# programmer-E01.net
KiCad netlist of a schematic drawn in EAGLE
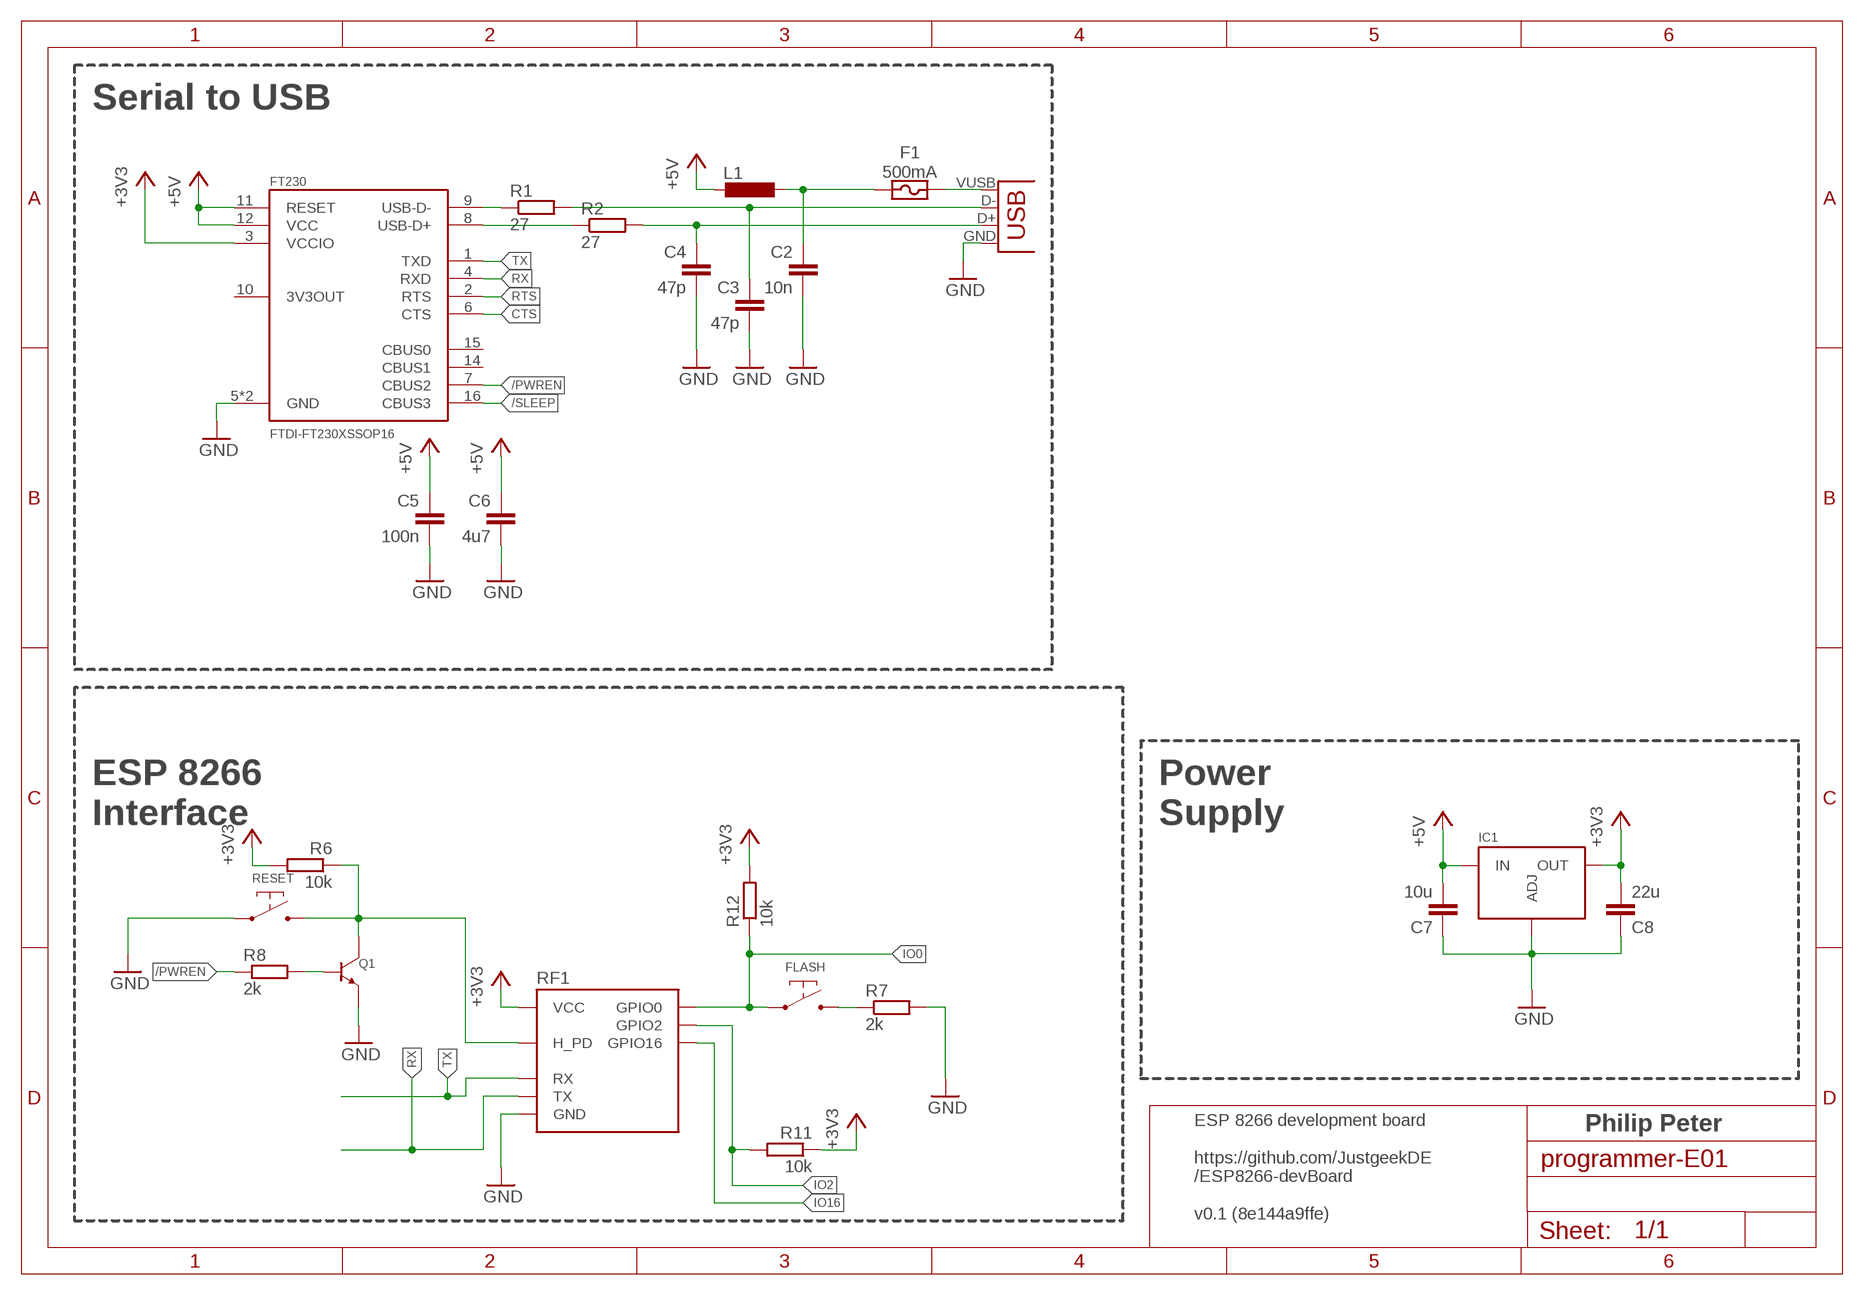
[diagram p0: schematic, sheet 1]

(export (version "E")
  (design (tool "Eeschema 10.0.6"))
  (components
    (comp (ref "C2")
      (value "10n")
      (footprint "eagle-import:C0805")
      (libsource (lib "eagle-import") (part "C-EUC0805"))
    )
    (comp (ref "C3")
      (value "47p")
      (footprint "eagle-import:C0805")
      (libsource (lib "eagle-import") (part "C-EUC0805"))
    )
    (comp (ref "C4")
      (value "47p")
      (footprint "eagle-import:C0805")
      (libsource (lib "eagle-import") (part "C-EUC0805"))
    )
    (comp (ref "C5")
      (value "100n")
      (footprint "eagle-import:C0805")
      (libsource (lib "eagle-import") (part "C-EUC0805"))
    )
    (comp (ref "C6")
      (value "4u7")
      (footprint "eagle-import:C0805")
      (libsource (lib "eagle-import") (part "C-EUC0805"))
    )
    (comp (ref "C7")
      (value "10u")
      (footprint "eagle-import:C0805")
      (libsource (lib "eagle-import") (part "C-EUC0805"))
    )
    (comp (ref "C8")
      (value "22u")
      (footprint "eagle-import:C0805")
      (libsource (lib "eagle-import") (part "C-EUC0805"))
    )
    (comp (ref "CON1")
      (value "USBMICRO-NO_CENTER-LONG_PADS")
      (footprint "eagle-import:USB-MICRO-SMD-NO_CENTER-LONG_PADS")
      (libsource (lib "eagle-import") (part "USBMICRO-NO_CENTER-LONG_PADS"))
    )
    (comp (ref "F1")
      (value "500mA")
      (footprint "eagle-import:SMD-FUSE-0805")
      (libsource (lib "eagle-import") (part "FUSE0805"))
    )
    (comp (ref "FLASH")
      (value "SWITCH-DEFAULT_OFF-2PIN")
      (footprint "eagle-import:SWITCH-GENERIC-2_PIN")
      (libsource (lib "eagle-import") (part "SWITCH-DEFAULT_OFF-2PIN"))
    )
    (comp (ref "FT230")
      (value "FTDI-FT230XSSOP16")
      (footprint "eagle-import:SSOP-16-FTDI")
      (libsource (lib "eagle-import") (part "FTDI-FT230XSSOP16"))
    )
    (comp (ref "IC1")
      (value "REGULATOR-LM317-SOT223")
      (footprint "eagle-import:SOT223")
      (libsource (lib "eagle-import") (part "REGULATOR-LM317-SOT223"))
    )
    (comp (ref "L1")
      (value "875-MI0805K601R-10")
      (footprint "eagle-import:R0805")
      (libsource (lib "eagle-import") (part "INDUCTOR0805"))
    )
    (comp (ref "Q1")
      (value "TRANSISTOR-NPN-GENERIC-SOT23-BEC")
      (footprint "eagle-import:SOT23")
      (libsource (lib "eagle-import") (part "TRANSISTOR-NPN-GENERIC-SOT23-BEC"))
    )
    (comp (ref "R1")
      (value "27")
      (footprint "eagle-import:R0805")
      (libsource (lib "eagle-import") (part "R-EU_R0805"))
    )
    (comp (ref "R2")
      (value "27")
      (footprint "eagle-import:R0805")
      (libsource (lib "eagle-import") (part "R-EU_R0805"))
    )
    (comp (ref "R6")
      (value "10k")
      (footprint "eagle-import:R0805")
      (libsource (lib "eagle-import") (part "R-EU_R0805"))
    )
    (comp (ref "R7")
      (value "2k")
      (footprint "eagle-import:R0805")
      (libsource (lib "eagle-import") (part "R-EU_R0805"))
    )
    (comp (ref "R8")
      (value "2k")
      (footprint "eagle-import:R0805")
      (libsource (lib "eagle-import") (part "R-EU_R0805"))
    )
    (comp (ref "R11")
      (value "10k")
      (footprint "eagle-import:R0805")
      (libsource (lib "eagle-import") (part "R-EU_R0805"))
    )
    (comp (ref "R12")
      (value "10k")
      (footprint "eagle-import:R0805")
      (libsource (lib "eagle-import") (part "R-EU_R0805"))
    )
    (comp (ref "RESET")
      (value "SWITCH-DEFAULT_OFF-2PIN")
      (footprint "eagle-import:SWITCH-GENERIC-2_PIN")
      (libsource (lib "eagle-import") (part "SWITCH-DEFAULT_OFF-2PIN"))
    )
    (comp (ref "RF1")
      (value "ESP2866-ESP-01THT")
      (footprint "eagle-import:ESP8266-ESP-01")
      (libsource (lib "eagle-import") (part "ESP2866-ESP-01THT"))
    )
  )
  (nets
    (net (code "1") (name "+3V3") (class "Default")
      (node (ref "C8") (pin "2") (pinfunction "2_2") (pintype "passive"))
      (node (ref "FT230") (pin "3") (pinfunction "VCCIO_3") (pintype "bidirectional"))
      (node (ref "IC1") (pin "2") (pinfunction "OUT_2") (pintype "bidirectional"))
      (node (ref "IC1") (pin "4") (pinfunction "OUT_4") (pintype "bidirectional"))
      (node (ref "R11") (pin "1") (pinfunction "1_1") (pintype "passive"))
      (node (ref "R12") (pin "2") (pinfunction "2_2") (pintype "passive"))
      (node (ref "R6") (pin "2") (pinfunction "2_2") (pintype "passive"))
      (node (ref "RF1") (pin "VCC") (pinfunction "VCC_VCC") (pintype "bidirectional"))
    )
    (net (code "2") (name "+5V") (class "Default")
      (node (ref "C5") (pin "1") (pinfunction "1_1") (pintype "passive"))
      (node (ref "C6") (pin "1") (pinfunction "1_1") (pintype "passive"))
      (node (ref "C7") (pin "2") (pinfunction "2_2") (pintype "passive"))
      (node (ref "FT230") (pin "11") (pinfunction "RESET_11") (pintype "bidirectional"))
      (node (ref "FT230") (pin "12") (pinfunction "VCC_12") (pintype "bidirectional"))
      (node (ref "IC1") (pin "3") (pinfunction "IN_3") (pintype "bidirectional"))
      (node (ref "L1") (pin "2") (pinfunction "2_2") (pintype "passive"))
    )
    (net (code "3") (name "CTS") (class "Default")
      (node (ref "FT230") (pin "6") (pinfunction "CTS_6") (pintype "bidirectional"))
    )
    (net (code "4") (name "GND") (class "Default")
      (node (ref "C2") (pin "2") (pinfunction "2_2") (pintype "passive"))
      (node (ref "C3") (pin "2") (pinfunction "2_2") (pintype "passive"))
      (node (ref "C4") (pin "2") (pinfunction "2_2") (pintype "passive"))
      (node (ref "C5") (pin "2") (pinfunction "2_2") (pintype "passive"))
      (node (ref "C6") (pin "2") (pinfunction "2_2") (pintype "passive"))
      (node (ref "C7") (pin "1") (pinfunction "1_1") (pintype "passive"))
      (node (ref "C8") (pin "1") (pinfunction "1_1") (pintype "passive"))
      (node (ref "CON1") (pin "GND") (pinfunction "GND_GND") (pintype "bidirectional"))
      (node (ref "FT230") (pin "13") (pinfunction "GND_13") (pintype "bidirectional"))
      (node (ref "FT230") (pin "5") (pinfunction "GND_5") (pintype "bidirectional"))
      (node (ref "IC1") (pin "1") (pinfunction "ADJ_1") (pintype "bidirectional"))
      (node (ref "Q1") (pin "P$2") (pinfunction "EMITTER_P$2") (pintype "bidirectional"))
      (node (ref "R7") (pin "2") (pinfunction "2_2") (pintype "passive"))
      (node (ref "RESET") (pin "P$1") (pinfunction "P$1_P$1") (pintype "bidirectional"))
      (node (ref "RF1") (pin "GND") (pinfunction "GND_GND") (pintype "bidirectional"))
    )
    (net (code "5") (name "IO0") (class "Default")
      (node (ref "FLASH") (pin "P$1") (pinfunction "P$1_P$1") (pintype "bidirectional"))
      (node (ref "R12") (pin "1") (pinfunction "1_1") (pintype "passive"))
      (node (ref "RF1") (pin "GPIO0") (pinfunction "GPIO0_GPIO0") (pintype "bidirectional"))
    )
    (net (code "6") (name "IO2") (class "Default")
      (node (ref "R11") (pin "2") (pinfunction "2_2") (pintype "passive"))
      (node (ref "RF1") (pin "GPIO2") (pinfunction "GPIO2_GPIO2") (pintype "bidirectional"))
    )
    (net (code "7") (name "IO16") (class "Default")
      (node (ref "RF1") (pin "GPIO16") (pinfunction "GPIO16_GPIO16") (pintype "bidirectional"))
    )
    (net (code "8") (name "Net-(C3-Pad1)") (class "Default")
      (node (ref "C3") (pin "1") (pinfunction "1_1") (pintype "passive"))
      (node (ref "CON1") (pin "D-") (pinfunction "D-_D-") (pintype "bidirectional"))
      (node (ref "R1") (pin "2") (pinfunction "2_2") (pintype "passive"))
    )
    (net (code "9") (name "Net-(C4-Pad1)") (class "Default")
      (node (ref "C4") (pin "1") (pinfunction "1_1") (pintype "passive"))
      (node (ref "CON1") (pin "D+") (pinfunction "D+_D+") (pintype "bidirectional"))
      (node (ref "R2") (pin "2") (pinfunction "2_2") (pintype "passive"))
    )
    (net (code "10") (name "Net-(CON1-VBUS)") (class "Default")
      (node (ref "CON1") (pin "VUSB") (pinfunction "VBUS_VUSB") (pintype "bidirectional"))
      (node (ref "F1") (pin "2") (pinfunction "P$2_2") (pintype "bidirectional"))
    )
    (net (code "11") (name "Net-(F1-P$1)") (class "Default")
      (node (ref "C2") (pin "1") (pinfunction "1_1") (pintype "passive"))
      (node (ref "F1") (pin "1") (pinfunction "P$1_1") (pintype "bidirectional"))
      (node (ref "L1") (pin "1") (pinfunction "1_1") (pintype "passive"))
    )
    (net (code "12") (name "Net-(FLASH-PadP$2)") (class "Default")
      (node (ref "FLASH") (pin "P$2") (pinfunction "P$2_P$2") (pintype "bidirectional"))
      (node (ref "R7") (pin "1") (pinfunction "1_1") (pintype "passive"))
    )
    (net (code "13") (name "Net-(FT230-USB-D+)") (class "Default")
      (node (ref "FT230") (pin "8") (pinfunction "USB-D+_8") (pintype "bidirectional"))
      (node (ref "R2") (pin "1") (pinfunction "1_1") (pintype "passive"))
    )
    (net (code "14") (name "Net-(FT230-USB-D-)") (class "Default")
      (node (ref "FT230") (pin "9") (pinfunction "USB-D-_9") (pintype "bidirectional"))
      (node (ref "R1") (pin "1") (pinfunction "1_1") (pintype "passive"))
    )
    (net (code "15") (name "Net-(Q1-BASE)") (class "Default")
      (node (ref "Q1") (pin "P$1") (pinfunction "BASE_P$1") (pintype "bidirectional"))
      (node (ref "R8") (pin "2") (pinfunction "2_2") (pintype "passive"))
    )
    (net (code "16") (name "Net-(Q1-COLLECTOR)") (class "Default")
      (node (ref "Q1") (pin "P$3") (pinfunction "COLLECTOR_P$3") (pintype "bidirectional"))
      (node (ref "R6") (pin "1") (pinfunction "1_1") (pintype "passive"))
      (node (ref "RESET") (pin "P$2") (pinfunction "P$2_P$2") (pintype "bidirectional"))
      (node (ref "RF1") (pin "H_PD") (pinfunction "H_PD_H_PD") (pintype "bidirectional"))
    )
    (net (code "17") (name "RTS") (class "Default")
      (node (ref "FT230") (pin "2") (pinfunction "RTS_2") (pintype "bidirectional"))
    )
    (net (code "18") (name "RX") (class "Default")
      (node (ref "FT230") (pin "4") (pinfunction "RXD_4") (pintype "bidirectional"))
      (node (ref "RF1") (pin "TX") (pinfunction "TX_TX") (pintype "bidirectional"))
    )
    (net (code "19") (name "TX") (class "Default")
      (node (ref "FT230") (pin "1") (pinfunction "TXD_1") (pintype "bidirectional"))
      (node (ref "RF1") (pin "RX") (pinfunction "RX_RX") (pintype "bidirectional"))
    )
    (net (code "20") (name "unconnected-(FT230-3V3OUT-Pad10)") (class "Default")
      (node (ref "FT230") (pin "10") (pinfunction "3V3OUT_10") (pintype "bidirectional"))
    )
    (net (code "21") (name "unconnected-(FT230-CBUS0-Pad15)") (class "Default")
      (node (ref "FT230") (pin "15") (pinfunction "CBUS0_15") (pintype "bidirectional"))
    )
    (net (code "22") (name "unconnected-(FT230-CBUS1-Pad14)") (class "Default")
      (node (ref "FT230") (pin "14") (pinfunction "CBUS1_14") (pintype "bidirectional"))
    )
    (net (code "23") (name "{slash}PWREN") (class "Default")
      (node (ref "FT230") (pin "7") (pinfunction "CBUS2_7") (pintype "bidirectional"))
      (node (ref "R8") (pin "1") (pinfunction "1_1") (pintype "passive"))
    )
    (net (code "24") (name "{slash}SLEEP") (class "Default")
      (node (ref "FT230") (pin "16") (pinfunction "CBUS3_16") (pintype "bidirectional"))
    )
  )
)
